# 10-AdditionalSensors.net
KiCad netlist of a schematic drawn in Altium Designer
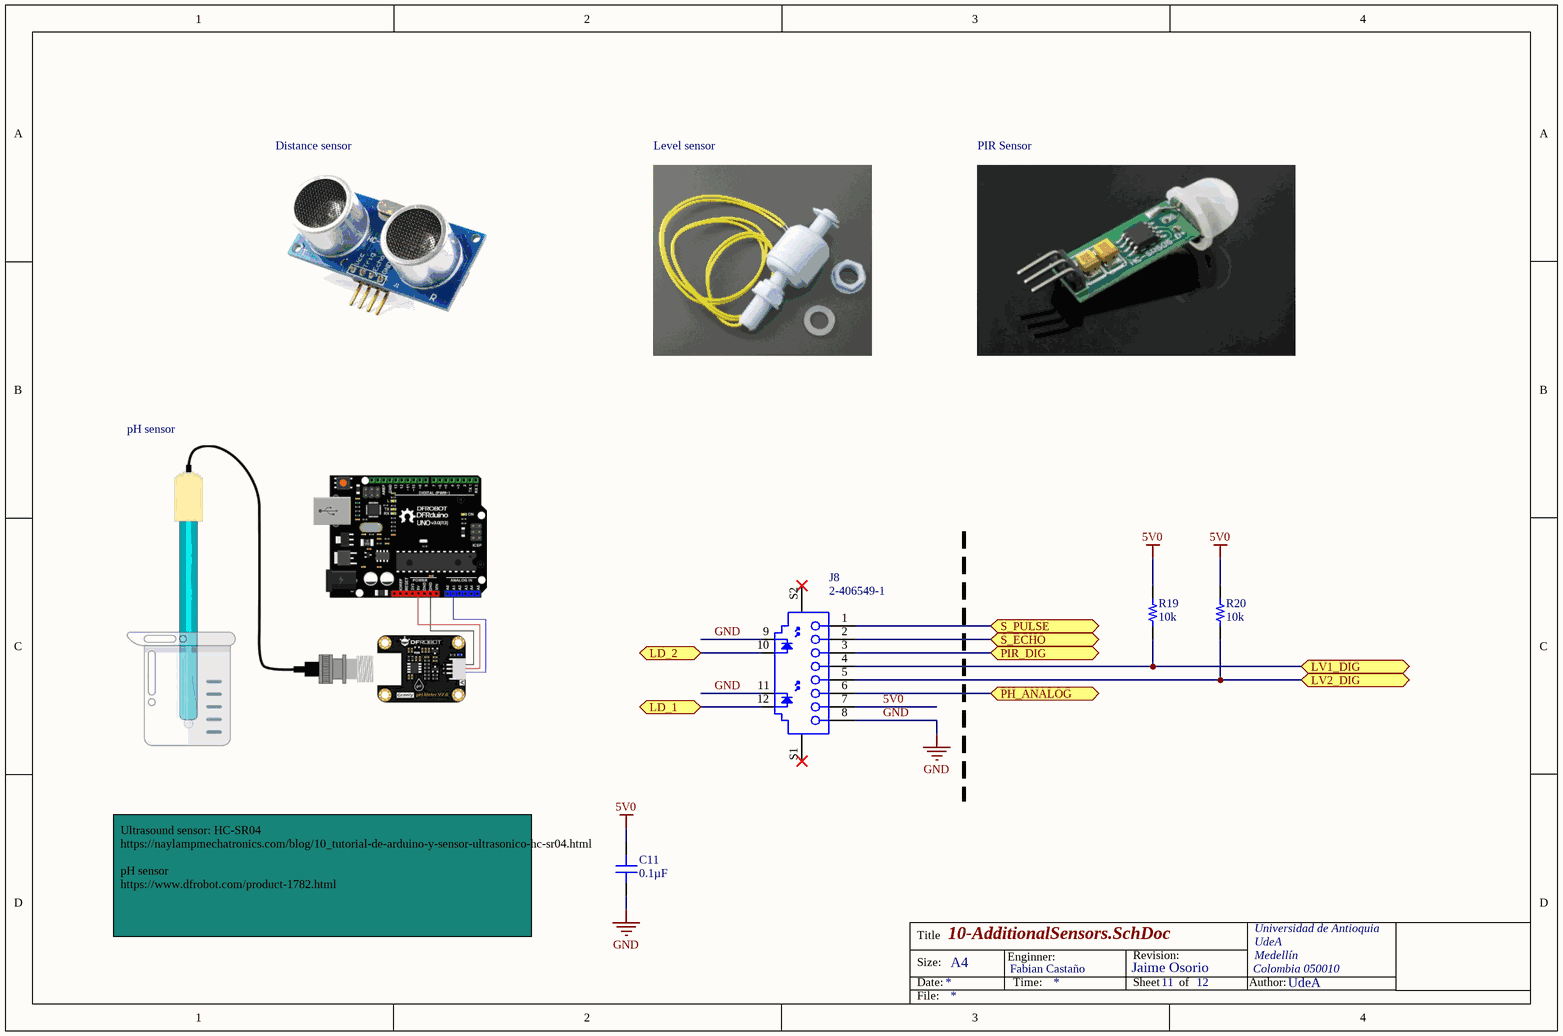
[diagram p0: 10-AdditionalSensors.SchDoc]

(export (version "E")
  (design (tool "Eeschema 10.0.6"))
  (components
    (comp (ref "C11")
      (value "0.1µF")
      (footprint "CAP 0805_2012")
      (description "CAP CER 0.1UF 50V X7R 0805")
      (fields (field (name "PART NUMBER") "C0805C104M5RACAUTO") (field (name "MANUFACTURER") "KEMET"))
      (libsource (lib "Celestial Altium Library - altium_library") (part "Capacitor"))
    )
    (comp (ref "J8")
      (value "2-406549-1")
      (footprint "TECO-2-406549-1_V")
      (description "RJ45 Connector, Pitch 1.016 mm, 8 Position, Height 14.22 mm, Tail Length 3.18 mm, RoHS, Tray")
      (fields (field (name "MANUFACTURER") "TE Connectivity"))
      (libsource (lib "Altium Content Vault") (part "RJ45-12-2SHLD_A"))
    )
    (comp (ref "R19")
      (value "10k")
      (footprint "RES 0805_2012")
      (description "RES SMD 1.47K OHM 1% 1/8W 0805")
      (fields (field (name "PART NUMBER") "RC0805FR-071K47L") (field (name "MANUFACTURER") "Yageo"))
      (libsource (lib "Celestial Altium Library - altium_library") (part "Resistor"))
    )
    (comp (ref "R20")
      (value "10k")
      (footprint "RES 0805_2012")
      (description "RES SMD 1.47K OHM 1% 1/8W 0805")
      (fields (field (name "PART NUMBER") "RC0805FR-071K47L") (field (name "MANUFACTURER") "Yageo"))
      (libsource (lib "Celestial Altium Library - altium_library") (part "Resistor"))
    )
  )
  (nets
    (net (code "1") (name "/LD_1") (class "Default")
      (node (ref "J8") (pin "12") (pinfunction "12_12") (pintype "passive"))
    )
    (net (code "2") (name "/LD_2") (class "Default")
      (node (ref "J8") (pin "10") (pinfunction "10_10") (pintype "passive"))
    )
    (net (code "3") (name "/LV1_DIG") (class "Default")
      (node (ref "J8") (pin "4") (pinfunction "4_4") (pintype "passive"))
      (node (ref "R19") (pin "1") (pinfunction "1_1") (pintype "passive"))
    )
    (net (code "4") (name "/LV2_DIG") (class "Default")
      (node (ref "J8") (pin "5") (pinfunction "5_5") (pintype "passive"))
      (node (ref "R20") (pin "1") (pinfunction "1_1") (pintype "passive"))
    )
    (net (code "5") (name "/PH_ANALOG") (class "Default")
      (node (ref "J8") (pin "6") (pinfunction "6_6") (pintype "passive"))
    )
    (net (code "6") (name "/PIR_DIG") (class "Default")
      (node (ref "J8") (pin "3") (pinfunction "3_3") (pintype "passive"))
    )
    (net (code "7") (name "/S_ECHO") (class "Default")
      (node (ref "J8") (pin "2") (pinfunction "2_2") (pintype "passive"))
    )
    (net (code "8") (name "/S_PULSE") (class "Default")
      (node (ref "J8") (pin "1") (pinfunction "1_1") (pintype "passive"))
    )
    (net (code "9") (name "5V0") (class "Default")
      (node (ref "C11") (pin "2") (pinfunction "2_2") (pintype "passive"))
      (node (ref "J8") (pin "7") (pinfunction "7_7") (pintype "passive"))
      (node (ref "R19") (pin "2") (pinfunction "2_2") (pintype "passive"))
      (node (ref "R20") (pin "2") (pinfunction "2_2") (pintype "passive"))
    )
    (net (code "10") (name "GND") (class "Default")
      (node (ref "C11") (pin "1") (pinfunction "1_1") (pintype "passive"))
      (node (ref "J8") (pin "11") (pinfunction "11_11") (pintype "passive"))
      (node (ref "J8") (pin "8") (pinfunction "8_8") (pintype "passive"))
      (node (ref "J8") (pin "9") (pinfunction "9_9") (pintype "passive"))
    )
    (net (code "11") (name "unconnected-(J8-PadS1)") (class "Default")
      (node (ref "J8") (pin "S1") (pinfunction "S1_S1") (pintype "passive+no_connect"))
    )
    (net (code "12") (name "unconnected-(J8-PadS2)") (class "Default")
      (node (ref "J8") (pin "S2") (pinfunction "S2_S2") (pintype "passive+no_connect"))
    )
  )
)
